# 2bitAdder.net
KiCad netlist of a schematic drawn in EAGLE
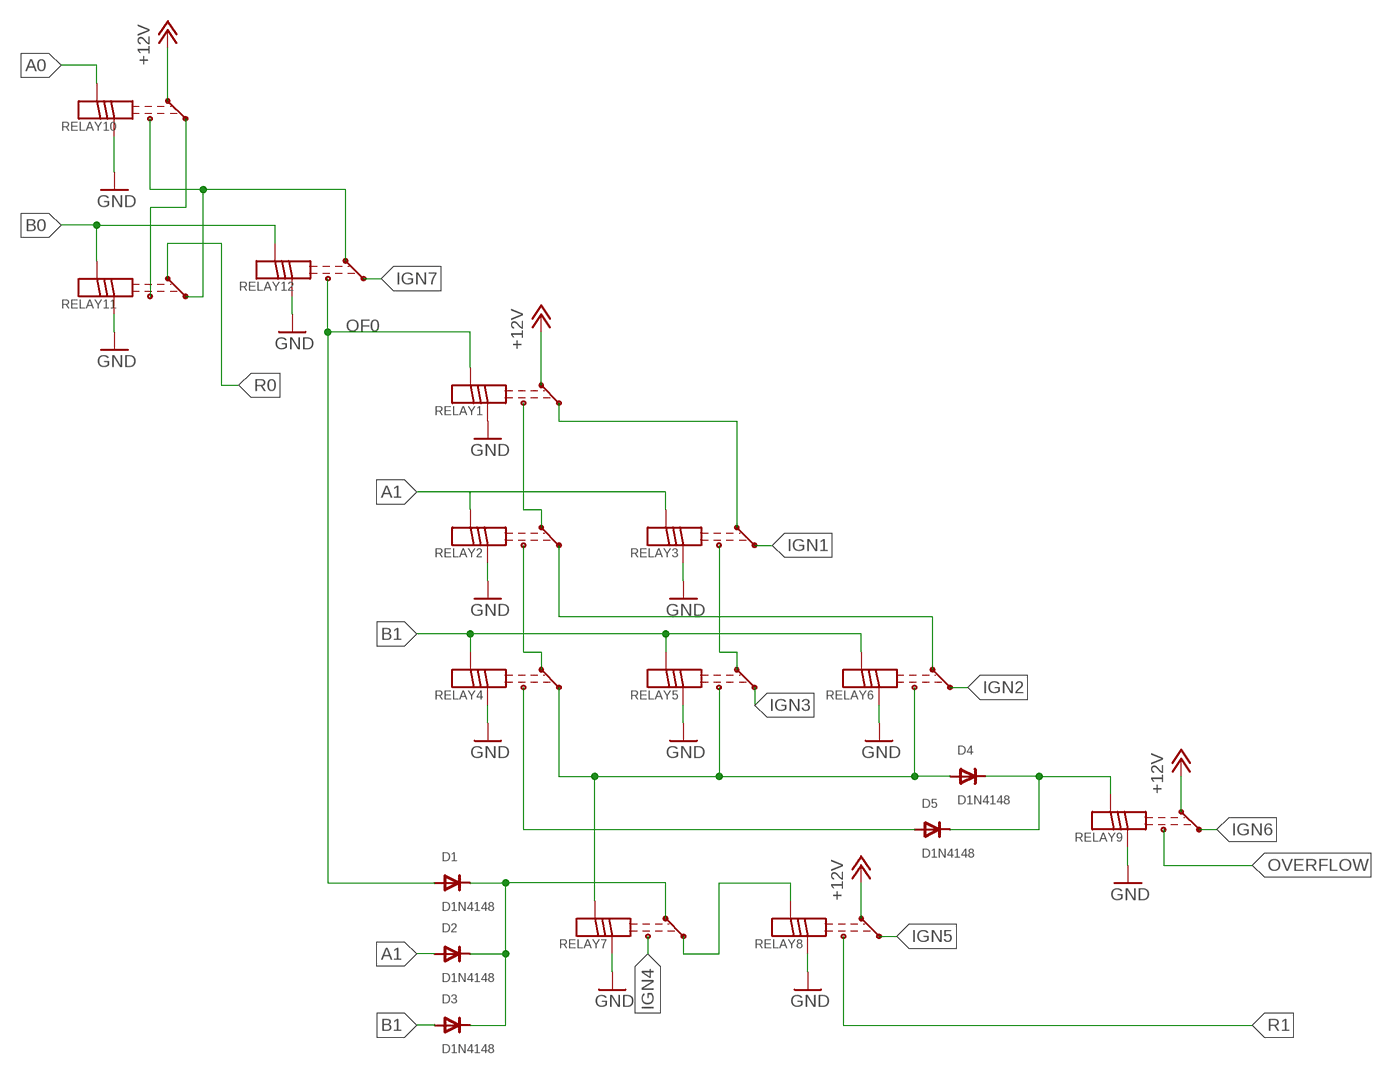
[diagram p0: schematic, sheet 1]

(export (version "E")
  (design (tool "Eeschema 10.0.6"))
  (components
    (comp (ref "D1")
      (value "D1N4148")
      (footprint "eagle-import:R0603")
      (libsource (lib "eagle-import") (part "DIODE"))
    )
    (comp (ref "D2")
      (value "D1N4148")
      (footprint "eagle-import:R0603")
      (libsource (lib "eagle-import") (part "DIODE"))
    )
    (comp (ref "D3")
      (value "D1N4148")
      (footprint "eagle-import:R0603")
      (libsource (lib "eagle-import") (part "DIODE"))
    )
    (comp (ref "D4")
      (value "D1N4148")
      (footprint "eagle-import:R0603")
      (libsource (lib "eagle-import") (part "DIODE"))
    )
    (comp (ref "D5")
      (value "D1N4148")
      (footprint "eagle-import:R0603")
      (libsource (lib "eagle-import") (part "DIODE"))
    )
    (comp (ref "RELAY1")
      (value "basicRelay")
      (footprint "eagle-import:RELAY-FINDER-40.51")
      (libsource (lib "eagle-import") (part "RELAY-GENERIC"))
    )
    (comp (ref "RELAY2")
      (value "basicRelay")
      (footprint "eagle-import:RELAY-FINDER-40.51")
      (libsource (lib "eagle-import") (part "RELAY-GENERIC"))
    )
    (comp (ref "RELAY3")
      (value "basicRelay")
      (footprint "eagle-import:RELAY-FINDER-40.51")
      (libsource (lib "eagle-import") (part "RELAY-GENERIC"))
    )
    (comp (ref "RELAY4")
      (value "basicRelay")
      (footprint "eagle-import:RELAY-FINDER-40.51")
      (libsource (lib "eagle-import") (part "RELAY-GENERIC"))
    )
    (comp (ref "RELAY5")
      (value "basicRelay")
      (footprint "eagle-import:RELAY-FINDER-40.51")
      (libsource (lib "eagle-import") (part "RELAY-GENERIC"))
    )
    (comp (ref "RELAY6")
      (value "basicRelay")
      (footprint "eagle-import:RELAY-FINDER-40.51")
      (libsource (lib "eagle-import") (part "RELAY-GENERIC"))
    )
    (comp (ref "RELAY7")
      (value "basicRelay")
      (footprint "eagle-import:RELAY-FINDER-40.51")
      (libsource (lib "eagle-import") (part "RELAY-GENERIC"))
    )
    (comp (ref "RELAY8")
      (value "basicRelay")
      (footprint "eagle-import:RELAY-FINDER-40.51")
      (libsource (lib "eagle-import") (part "RELAY-GENERIC"))
    )
    (comp (ref "RELAY9")
      (value "basicRelay")
      (footprint "eagle-import:RELAY-FINDER-40.51")
      (libsource (lib "eagle-import") (part "RELAY-GENERIC"))
    )
    (comp (ref "RELAY10")
      (value "basicRelay")
      (footprint "eagle-import:RELAY-FINDER-40.51")
      (libsource (lib "eagle-import") (part "RELAY-GENERIC"))
    )
    (comp (ref "RELAY11")
      (value "basicRelay")
      (footprint "eagle-import:RELAY-FINDER-40.51")
      (libsource (lib "eagle-import") (part "RELAY-GENERIC"))
    )
    (comp (ref "RELAY12")
      (value "basicRelay")
      (footprint "eagle-import:RELAY-FINDER-40.51")
      (libsource (lib "eagle-import") (part "RELAY-GENERIC"))
    )
  )
  (nets
    (net (code "1") (name "+12V") (class "Default")
      (node (ref "RELAY1") (pin "CENTER") (pinfunction "CENTER_CENTER") (pintype "bidirectional"))
      (node (ref "RELAY10") (pin "CENTER") (pinfunction "CENTER_CENTER") (pintype "bidirectional"))
      (node (ref "RELAY8") (pin "CENTER") (pinfunction "CENTER_CENTER") (pintype "bidirectional"))
      (node (ref "RELAY9") (pin "CENTER") (pinfunction "CENTER_CENTER") (pintype "bidirectional"))
    )
    (net (code "2") (name "/OF0") (class "Default")
      (node (ref "D1") (pin "1") (pinfunction "ANODE_1") (pintype "bidirectional"))
      (node (ref "RELAY1") (pin "N+") (pinfunction "N+_N+") (pintype "bidirectional"))
      (node (ref "RELAY12") (pin "NOP") (pinfunction "NOP_NOP") (pintype "bidirectional"))
    )
    (net (code "3") (name "A0") (class "Default")
      (node (ref "RELAY10") (pin "N+") (pinfunction "N+_N+") (pintype "bidirectional"))
    )
    (net (code "4") (name "A1") (class "Default")
      (node (ref "D2") (pin "1") (pinfunction "ANODE_1") (pintype "bidirectional"))
      (node (ref "RELAY2") (pin "N+") (pinfunction "N+_N+") (pintype "bidirectional"))
      (node (ref "RELAY3") (pin "N+") (pinfunction "N+_N+") (pintype "bidirectional"))
    )
    (net (code "5") (name "B0") (class "Default")
      (node (ref "RELAY11") (pin "N+") (pinfunction "N+_N+") (pintype "bidirectional"))
      (node (ref "RELAY12") (pin "N+") (pinfunction "N+_N+") (pintype "bidirectional"))
    )
    (net (code "6") (name "B1") (class "Default")
      (node (ref "D3") (pin "1") (pinfunction "ANODE_1") (pintype "bidirectional"))
      (node (ref "RELAY4") (pin "N+") (pinfunction "N+_N+") (pintype "bidirectional"))
      (node (ref "RELAY5") (pin "N+") (pinfunction "N+_N+") (pintype "bidirectional"))
      (node (ref "RELAY6") (pin "N+") (pinfunction "N+_N+") (pintype "bidirectional"))
    )
    (net (code "7") (name "GND") (class "Default")
      (node (ref "RELAY1") (pin "N-") (pinfunction "N-_N-") (pintype "bidirectional"))
      (node (ref "RELAY10") (pin "N-") (pinfunction "N-_N-") (pintype "bidirectional"))
      (node (ref "RELAY11") (pin "N-") (pinfunction "N-_N-") (pintype "bidirectional"))
      (node (ref "RELAY12") (pin "N-") (pinfunction "N-_N-") (pintype "bidirectional"))
      (node (ref "RELAY2") (pin "N-") (pinfunction "N-_N-") (pintype "bidirectional"))
      (node (ref "RELAY3") (pin "N-") (pinfunction "N-_N-") (pintype "bidirectional"))
      (node (ref "RELAY4") (pin "N-") (pinfunction "N-_N-") (pintype "bidirectional"))
      (node (ref "RELAY5") (pin "N-") (pinfunction "N-_N-") (pintype "bidirectional"))
      (node (ref "RELAY6") (pin "N-") (pinfunction "N-_N-") (pintype "bidirectional"))
      (node (ref "RELAY7") (pin "N-") (pinfunction "N-_N-") (pintype "bidirectional"))
      (node (ref "RELAY8") (pin "N-") (pinfunction "N-_N-") (pintype "bidirectional"))
      (node (ref "RELAY9") (pin "N-") (pinfunction "N-_N-") (pintype "bidirectional"))
    )
    (net (code "8") (name "IGN1") (class "Default")
      (node (ref "RELAY3") (pin "NCL") (pinfunction "NCL_NCL") (pintype "bidirectional"))
    )
    (net (code "9") (name "IGN2") (class "Default")
      (node (ref "RELAY6") (pin "NCL") (pinfunction "NCL_NCL") (pintype "bidirectional"))
    )
    (net (code "10") (name "IGN3") (class "Default")
      (node (ref "RELAY5") (pin "NCL") (pinfunction "NCL_NCL") (pintype "bidirectional"))
    )
    (net (code "11") (name "IGN4") (class "Default")
      (node (ref "RELAY7") (pin "NOP") (pinfunction "NOP_NOP") (pintype "bidirectional"))
    )
    (net (code "12") (name "IGN5") (class "Default")
      (node (ref "RELAY8") (pin "NCL") (pinfunction "NCL_NCL") (pintype "bidirectional"))
    )
    (net (code "13") (name "IGN6") (class "Default")
      (node (ref "RELAY9") (pin "NCL") (pinfunction "NCL_NCL") (pintype "bidirectional"))
    )
    (net (code "14") (name "IGN7") (class "Default")
      (node (ref "RELAY12") (pin "NCL") (pinfunction "NCL_NCL") (pintype "bidirectional"))
    )
    (net (code "15") (name "Net-(D1-CATHODE)") (class "Default")
      (node (ref "D1") (pin "2") (pinfunction "CATHODE_2") (pintype "bidirectional"))
      (node (ref "D2") (pin "2") (pinfunction "CATHODE_2") (pintype "bidirectional"))
      (node (ref "D3") (pin "2") (pinfunction "CATHODE_2") (pintype "bidirectional"))
      (node (ref "RELAY7") (pin "CENTER") (pinfunction "CENTER_CENTER") (pintype "bidirectional"))
    )
    (net (code "16") (name "Net-(D4-ANODE)") (class "Default")
      (node (ref "D4") (pin "1") (pinfunction "ANODE_1") (pintype "bidirectional"))
      (node (ref "RELAY4") (pin "NCL") (pinfunction "NCL_NCL") (pintype "bidirectional"))
      (node (ref "RELAY5") (pin "NOP") (pinfunction "NOP_NOP") (pintype "bidirectional"))
      (node (ref "RELAY6") (pin "NOP") (pinfunction "NOP_NOP") (pintype "bidirectional"))
      (node (ref "RELAY7") (pin "N+") (pinfunction "N+_N+") (pintype "bidirectional"))
    )
    (net (code "17") (name "Net-(D4-CATHODE)") (class "Default")
      (node (ref "D4") (pin "2") (pinfunction "CATHODE_2") (pintype "bidirectional"))
      (node (ref "D5") (pin "2") (pinfunction "CATHODE_2") (pintype "bidirectional"))
      (node (ref "RELAY9") (pin "N+") (pinfunction "N+_N+") (pintype "bidirectional"))
    )
    (net (code "18") (name "Net-(D5-ANODE)") (class "Default")
      (node (ref "D5") (pin "1") (pinfunction "ANODE_1") (pintype "bidirectional"))
      (node (ref "RELAY4") (pin "NOP") (pinfunction "NOP_NOP") (pintype "bidirectional"))
    )
    (net (code "19") (name "Net-(RELAY1-PadNCL)") (class "Default")
      (node (ref "RELAY1") (pin "NCL") (pinfunction "NCL_NCL") (pintype "bidirectional"))
      (node (ref "RELAY3") (pin "CENTER") (pinfunction "CENTER_CENTER") (pintype "bidirectional"))
    )
    (net (code "20") (name "Net-(RELAY1-PadNOP)") (class "Default")
      (node (ref "RELAY1") (pin "NOP") (pinfunction "NOP_NOP") (pintype "bidirectional"))
      (node (ref "RELAY2") (pin "CENTER") (pinfunction "CENTER_CENTER") (pintype "bidirectional"))
    )
    (net (code "21") (name "Net-(RELAY2-PadNCL)") (class "Default")
      (node (ref "RELAY2") (pin "NCL") (pinfunction "NCL_NCL") (pintype "bidirectional"))
      (node (ref "RELAY6") (pin "CENTER") (pinfunction "CENTER_CENTER") (pintype "bidirectional"))
    )
    (net (code "22") (name "Net-(RELAY2-PadNOP)") (class "Default")
      (node (ref "RELAY2") (pin "NOP") (pinfunction "NOP_NOP") (pintype "bidirectional"))
      (node (ref "RELAY4") (pin "CENTER") (pinfunction "CENTER_CENTER") (pintype "bidirectional"))
    )
    (net (code "23") (name "Net-(RELAY3-PadNOP)") (class "Default")
      (node (ref "RELAY3") (pin "NOP") (pinfunction "NOP_NOP") (pintype "bidirectional"))
      (node (ref "RELAY5") (pin "CENTER") (pinfunction "CENTER_CENTER") (pintype "bidirectional"))
    )
    (net (code "24") (name "Net-(RELAY7-PadNCL)") (class "Default")
      (node (ref "RELAY7") (pin "NCL") (pinfunction "NCL_NCL") (pintype "bidirectional"))
      (node (ref "RELAY8") (pin "N+") (pinfunction "N+_N+") (pintype "bidirectional"))
    )
    (net (code "25") (name "Net-(RELAY10-PadNCL)") (class "Default")
      (node (ref "RELAY10") (pin "NCL") (pinfunction "NCL_NCL") (pintype "bidirectional"))
      (node (ref "RELAY11") (pin "NOP") (pinfunction "NOP_NOP") (pintype "bidirectional"))
    )
    (net (code "26") (name "Net-(RELAY10-PadNOP)") (class "Default")
      (node (ref "RELAY10") (pin "NOP") (pinfunction "NOP_NOP") (pintype "bidirectional"))
      (node (ref "RELAY11") (pin "NCL") (pinfunction "NCL_NCL") (pintype "bidirectional"))
      (node (ref "RELAY12") (pin "CENTER") (pinfunction "CENTER_CENTER") (pintype "bidirectional"))
    )
    (net (code "27") (name "OVERFLOW") (class "Default")
      (node (ref "RELAY9") (pin "NOP") (pinfunction "NOP_NOP") (pintype "bidirectional"))
    )
    (net (code "28") (name "R0") (class "Default")
      (node (ref "RELAY11") (pin "CENTER") (pinfunction "CENTER_CENTER") (pintype "bidirectional"))
    )
    (net (code "29") (name "R1") (class "Default")
      (node (ref "RELAY8") (pin "NOP") (pinfunction "NOP_NOP") (pintype "bidirectional"))
    )
  )
)
